# OZ440-SE100-CAR003_sheet14.net
KiCad netlist of a schematic drawn in Altium Designer
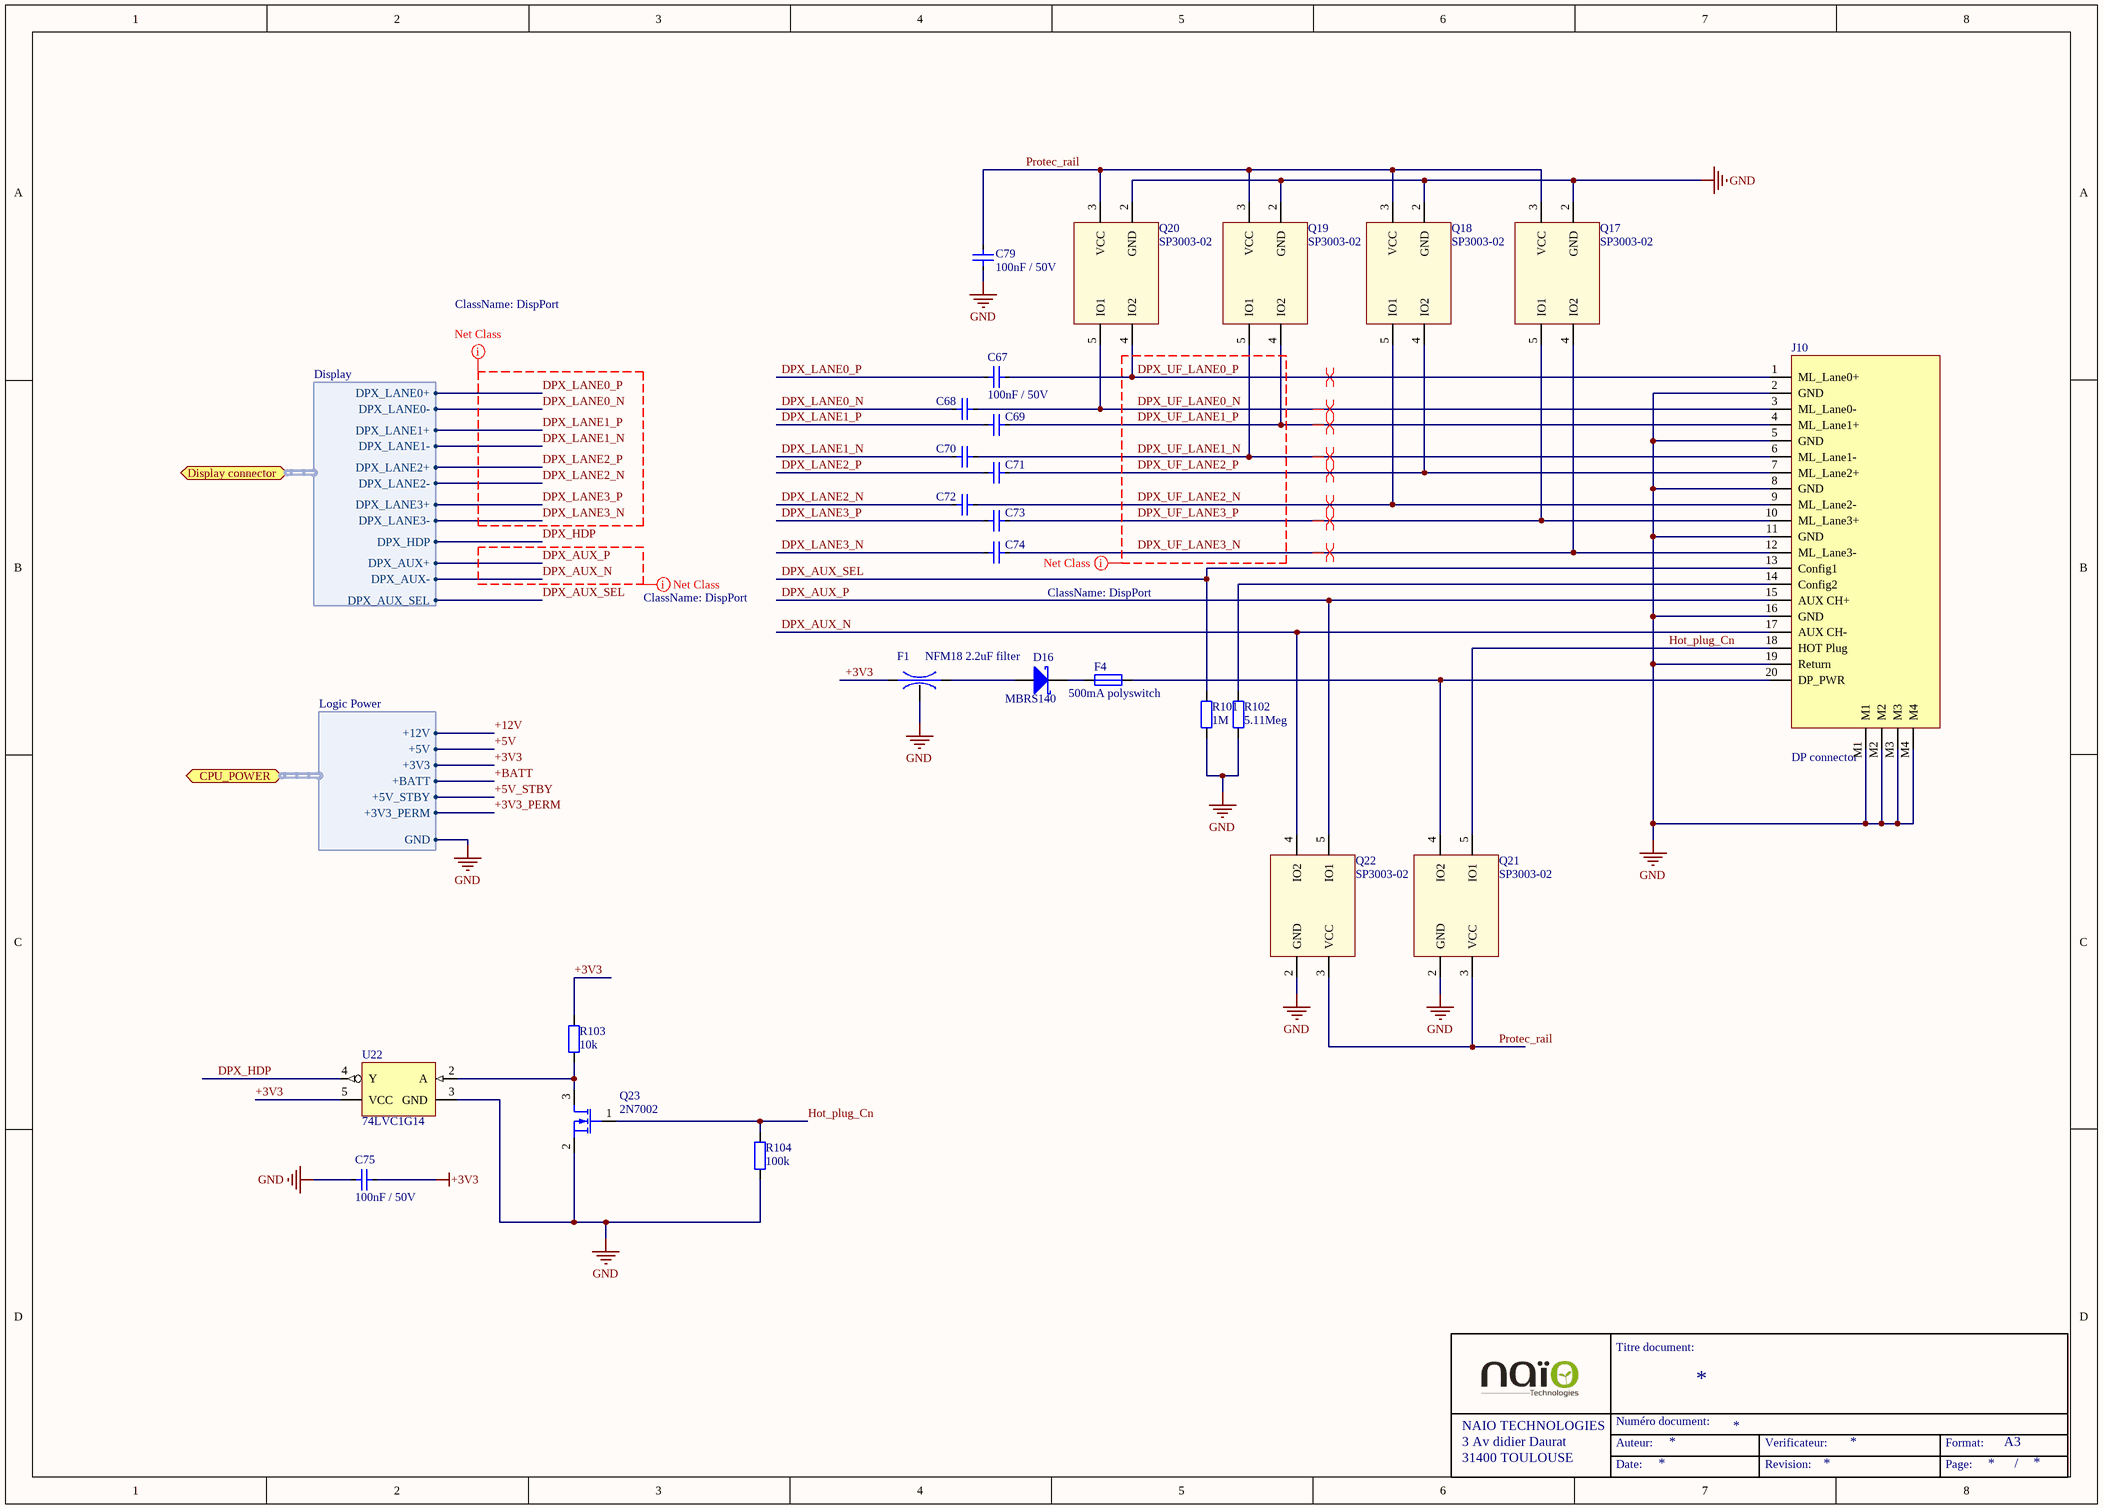
[diagram p0: OZ440-SE100-CAR003_sheet14.SchDoc]

(export (version "E")
  (design (tool "Eeschema 10.0.6"))
  (components
    (comp (ref "C67")
      (value "CAP-SMD")
      (footprint "C0805-STD")
      (description "0805 100nF / 50V  X7R ceramic capacitor")
      (fields
        (field (name "DISPLAYED REFERENCE") "100nF / 50V")
        (field (name "TOLERANCE") "+/- 10%")
        (field (name "MANUFACTURER") "vishay")
      )
      (libsource (lib "lib_NAIO") (part "CAP-SMD"))
    )
    (comp (ref "C68")
      (value "CAP-SMD")
      (footprint "C0805-STD")
      (description "0805 100nF / 50V  X7R ceramic capacitor")
      (fields (field (name "TOLERANCE") "+/- 10%") (field (name "MANUFACTURER") "vishay"))
      (libsource (lib "lib_NAIO") (part "CAP-SMD"))
    )
    (comp (ref "C69")
      (value "CAP-SMD")
      (footprint "C0805-STD")
      (description "0805 100nF / 50V  X7R ceramic capacitor")
      (fields (field (name "TOLERANCE") "+/- 10%") (field (name "MANUFACTURER") "vishay"))
      (libsource (lib "lib_NAIO") (part "CAP-SMD"))
    )
    (comp (ref "C70")
      (value "CAP-SMD")
      (footprint "C0805-STD")
      (description "0805 100nF / 50V  X7R ceramic capacitor")
      (fields (field (name "TOLERANCE") "+/- 10%") (field (name "MANUFACTURER") "vishay"))
      (libsource (lib "lib_NAIO") (part "CAP-SMD"))
    )
    (comp (ref "C71")
      (value "CAP-SMD")
      (footprint "C0805-STD")
      (description "0805 100nF / 50V  X7R ceramic capacitor")
      (fields (field (name "TOLERANCE") "+/- 10%") (field (name "MANUFACTURER") "vishay"))
      (libsource (lib "lib_NAIO") (part "CAP-SMD"))
    )
    (comp (ref "C72")
      (value "CAP-SMD")
      (footprint "C0805-STD")
      (description "0805 100nF / 50V  X7R ceramic capacitor")
      (fields (field (name "TOLERANCE") "+/- 10%") (field (name "MANUFACTURER") "vishay"))
      (libsource (lib "lib_NAIO") (part "CAP-SMD"))
    )
    (comp (ref "C73")
      (value "CAP-SMD")
      (footprint "C0805-STD")
      (description "0805 100nF / 50V  X7R ceramic capacitor")
      (fields (field (name "TOLERANCE") "+/- 10%") (field (name "MANUFACTURER") "vishay"))
      (libsource (lib "lib_NAIO") (part "CAP-SMD"))
    )
    (comp (ref "C74")
      (value "CAP-SMD")
      (footprint "C0805-STD")
      (description "0805 100nF / 50V  X7R ceramic capacitor")
      (fields (field (name "TOLERANCE") "+/- 10%") (field (name "MANUFACTURER") "vishay"))
      (libsource (lib "lib_NAIO") (part "CAP-SMD"))
    )
    (comp (ref "C75")
      (value "CAP-SMD")
      (footprint "C0805-STD")
      (description "0805 100nF / 50V  X7R ceramic capacitor")
      (fields
        (field (name "DISPLAYED REFERENCE") "100nF / 50V")
        (field (name "TOLERANCE") "+/- 10%")
        (field (name "MANUFACTURER") "vishay")
      )
      (libsource (lib "lib_NAIO") (part "CAP-SMD"))
    )
    (comp (ref "C79")
      (value "CAP-SMD")
      (footprint "C0805-STD")
      (description "0805 100nF / 50V  X7R ceramic capacitor")
      (fields
        (field (name "DISPLAYED REFERENCE") "100nF / 50V")
        (field (name "TOLERANCE") "+/- 10%")
        (field (name "MANUFACTURER") "vishay")
      )
      (libsource (lib "lib_NAIO") (part "CAP-SMD"))
    )
    (comp (ref "D16")
      (value "DIODE_SCHOTKY-DO214AA")
      (footprint "DO214AA-STD")
      (description "1A/40V shottky diode in SMB package")
      (fields (field (name "DISPLAYED REFERENCE") "MBRS140") (field (name "MANUFACTURER") "FAIRCHILD"))
      (libsource (lib "lib_NAIO") (part "DIODE_SCHOTKY-DO214AA"))
    )
    (comp (ref "F1")
      (value "LC_FILTER-STD")
      (footprint "LC_0603-STD")
      (description "2A LC filter")
      (fields
        (field (name "DISPLAYED REFERENCE") "NFM18 2.2uF filter")
        (field (name "MANUFACTURER") "MURATA")
      )
      (libsource (lib "lib_NAIO") (part "LC_FILTER-STD"))
    )
    (comp (ref "F4")
      (value "FUSE-SMD")
      (footprint "R0805-STD")
      (description "0805 500mA resettable fuse")
      (fields (field (name "DISPLAYED REFERENCE") "500mA polyswitch") (field (name "MANUFACTURER") "BOURNS"))
      (libsource (lib "lib_NAIO") (part "FUSE-SMD"))
    )
    (comp (ref "J10")
      (value "CONN-STD-DISPLAY_PORT_B")
      (footprint "CONN-SPE-DISPLAY_PORT_DP1RD20JQ1R400_JAE")
      (description "Display port PCB connector")
      (fields (field (name "DISPLAYED REFERENCE") "DP connector") (field (name "MANUFACTURER") "JAE"))
      (libsource (lib "lib_NAIO") (part "CONN-STD-DISPLAY_PORT_B"))
    )
    (comp (ref "Q17")
      (value "SP03003_02-SC70")
      (footprint "SC70-SPE-SP3003")
      (description "Low capacitance ESD TVS")
      (fields (field (name "DISPLAYED REFERENCE") "SP3003-02") (field (name "MANUFACTURER") "LITTLEFUSE"))
      (libsource (lib "lib_NAIO") (part "SP03003_02-SC70"))
    )
    (comp (ref "Q18")
      (value "SP03003_02-SC70")
      (footprint "SC70-SPE-SP3003")
      (description "Low capacitance ESD TVS")
      (fields (field (name "DISPLAYED REFERENCE") "SP3003-02") (field (name "MANUFACTURER") "LITTLEFUSE"))
      (libsource (lib "lib_NAIO") (part "SP03003_02-SC70"))
    )
    (comp (ref "Q19")
      (value "SP03003_02-SC70")
      (footprint "SC70-SPE-SP3003")
      (description "Low capacitance ESD TVS")
      (fields (field (name "DISPLAYED REFERENCE") "SP3003-02") (field (name "MANUFACTURER") "LITTLEFUSE"))
      (libsource (lib "lib_NAIO") (part "SP03003_02-SC70"))
    )
    (comp (ref "Q20")
      (value "SP03003_02-SC70")
      (footprint "SC70-SPE-SP3003")
      (description "Low capacitance ESD TVS")
      (fields (field (name "DISPLAYED REFERENCE") "SP3003-02") (field (name "MANUFACTURER") "LITTLEFUSE"))
      (libsource (lib "lib_NAIO") (part "SP03003_02-SC70"))
    )
    (comp (ref "Q21")
      (value "SP03003_02-SC70")
      (footprint "SC70-SPE-SP3003")
      (description "Low capacitance ESD TVS")
      (fields (field (name "DISPLAYED REFERENCE") "SP3003-02") (field (name "MANUFACTURER") "LITTLEFUSE"))
      (libsource (lib "") (part "SP03003_02-SC70_1"))
    )
    (comp (ref "Q22")
      (value "SP03003_02-SC70")
      (footprint "SC70-SPE-SP3003")
      (description "Low capacitance ESD TVS")
      (fields (field (name "DISPLAYED REFERENCE") "SP3003-02") (field (name "MANUFACTURER") "LITTLEFUSE"))
      (libsource (lib "") (part "SP03003_02-SC70_1"))
    )
    (comp (ref "Q23")
      (value "2N7002-SMD3P")
      (footprint "SOT23-SPE-2N7002")
      (description "N-Channel Enhancement Mode Field Effect Transistor")
      (fields (field (name "DISPLAYED REFERENCE") "2N7002") (field (name "MANUFACTURER") "FAIRCHILD"))
      (libsource (lib "lib_NAIO") (part "2N7002-SMD3P"))
    )
    (comp (ref "R101")
      (value "RES-SMD")
      (footprint "R0805-STD")
      (description "1Mohm 1% 0805 SMD resistor")
      (fields
        (field (name "DISPLAYED REFERENCE") "1M")
        (field (name "TOLERANCE") "1%")
        (field (name "MANUFACTURER") "Vishay")
      )
      (libsource (lib "lib_NAIO") (part "RES-SMD"))
    )
    (comp (ref "R102")
      (value "RES-SMD")
      (footprint "R0805-STD")
      (description "5.11Meg Ohm 0805 SMD resistor")
      (fields
        (field (name "DISPLAYED REFERENCE") "5.11Meg")
        (field (name "TOLERANCE") "1%")
        (field (name "MANUFACTURER") "Vishay")
      )
      (libsource (lib "lib_NAIO") (part "RES-SMD"))
    )
    (comp (ref "R103")
      (value "RES-SMD")
      (footprint "R0805-STD")
      (description "10k Ohm 0805 SMD resistor")
      (fields
        (field (name "DISPLAYED REFERENCE") "10k")
        (field (name "TOLERANCE") "1 %")
        (field (name "MANUFACTURER") "Vishay")
      )
      (libsource (lib "lib_NAIO") (part "RES-SMD"))
    )
    (comp (ref "R104")
      (value "RES-SMD")
      (footprint "R0805-STD")
      (description "100k Ohm 0805 SMD resistor")
      (fields
        (field (name "DISPLAYED REFERENCE") "100k")
        (field (name "TOLERANCE") "1 %")
        (field (name "MANUFACTURER") "Vishay")
      )
      (libsource (lib "lib_NAIO") (part "RES-SMD"))
    )
    (comp (ref "U22")
      (value "74xxx1G14GW-SOT353-1")
      (footprint "SOT353-1_5pin-STD")
      (description "smith trigger inverter")
      (fields (field (name "DISPLAYED REFERENCE") "74LVC1G14") (field (name "MANUFACTURER") "NXP"))
      (libsource (lib "lib_NAIO") (part "74xxx1G14GW-SOT353-1"))
    )
  )
  (nets
    (net (code "4") (name "+3V3") (class "Default")
      (node (ref "C75") (pin "2") (pinfunction "2_2") (pintype "passive"))
      (node (ref "F1") (pin "1") (pinfunction "A_1") (pintype "passive"))
      (node (ref "R103") (pin "2") (pinfunction "2_2") (pintype "passive"))
      (node (ref "U22") (pin "5") (pinfunction "VCC_5") (pintype "power_in"))
    )
    (net (code "10") (name "/DPX_AUX_N") (class "Default")
      (node (ref "J10") (pin "17") (pinfunction "AUX_CH-_17") (pintype "passive"))
      (node (ref "Q22") (pin "4") (pinfunction "IO2_4") (pintype "passive"))
    )
    (net (code "11") (name "/DPX_AUX_P") (class "Default")
      (node (ref "J10") (pin "15") (pinfunction "AUX_CH+_15") (pintype "passive"))
      (node (ref "Q22") (pin "5") (pinfunction "IO1_5") (pintype "passive"))
    )
    (net (code "12") (name "/DPX_AUX_SEL") (class "Default")
      (node (ref "J10") (pin "13") (pinfunction "Config1_13") (pintype "passive"))
      (node (ref "R101") (pin "2") (pinfunction "2_2") (pintype "passive"))
    )
    (net (code "13") (name "/DPX_HDP") (class "Default")
      (node (ref "U22") (pin "4") (pinfunction "Y_4") (pintype "output"))
    )
    (net (code "14") (name "/DPX_LANE0_N") (class "Default")
      (node (ref "C68") (pin "2") (pinfunction "2_2") (pintype "passive"))
    )
    (net (code "15") (name "/DPX_LANE0_P") (class "Default")
      (node (ref "C67") (pin "2") (pinfunction "2_2") (pintype "passive"))
    )
    (net (code "16") (name "/DPX_LANE1_N") (class "Default")
      (node (ref "C70") (pin "2") (pinfunction "2_2") (pintype "passive"))
    )
    (net (code "17") (name "/DPX_LANE1_P") (class "Default")
      (node (ref "C69") (pin "2") (pinfunction "2_2") (pintype "passive"))
    )
    (net (code "18") (name "/DPX_LANE2_N") (class "Default")
      (node (ref "C72") (pin "2") (pinfunction "2_2") (pintype "passive"))
    )
    (net (code "19") (name "/DPX_LANE2_P") (class "Default")
      (node (ref "C71") (pin "2") (pinfunction "2_2") (pintype "passive"))
    )
    (net (code "20") (name "/DPX_LANE3_N") (class "Default")
      (node (ref "C74") (pin "2") (pinfunction "2_2") (pintype "passive"))
    )
    (net (code "21") (name "/DPX_LANE3_P") (class "Default")
      (node (ref "C73") (pin "2") (pinfunction "2_2") (pintype "passive"))
    )
    (net (code "22") (name "/DPX_UF_LANE0_N") (class "Default")
      (node (ref "C68") (pin "1") (pinfunction "1_1") (pintype "passive"))
      (node (ref "J10") (pin "3") (pinfunction "ML_Lane0-_3") (pintype "passive"))
      (node (ref "Q20") (pin "5") (pinfunction "IO1_5") (pintype "passive"))
    )
    (net (code "23") (name "/DPX_UF_LANE0_P") (class "Default")
      (node (ref "C67") (pin "1") (pinfunction "1_1") (pintype "passive"))
      (node (ref "J10") (pin "1") (pinfunction "ML_Lane0+_1") (pintype "passive"))
      (node (ref "Q20") (pin "4") (pinfunction "IO2_4") (pintype "passive"))
    )
    (net (code "24") (name "/DPX_UF_LANE1_N") (class "Default")
      (node (ref "C70") (pin "1") (pinfunction "1_1") (pintype "passive"))
      (node (ref "J10") (pin "6") (pinfunction "ML_Lane1-_6") (pintype "passive"))
      (node (ref "Q19") (pin "5") (pinfunction "IO1_5") (pintype "passive"))
    )
    (net (code "25") (name "/DPX_UF_LANE1_P") (class "Default")
      (node (ref "C69") (pin "1") (pinfunction "1_1") (pintype "passive"))
      (node (ref "J10") (pin "4") (pinfunction "ML_Lane1+_4") (pintype "passive"))
      (node (ref "Q19") (pin "4") (pinfunction "IO2_4") (pintype "passive"))
    )
    (net (code "26") (name "/DPX_UF_LANE2_N") (class "Default")
      (node (ref "C72") (pin "1") (pinfunction "1_1") (pintype "passive"))
      (node (ref "J10") (pin "9") (pinfunction "ML_Lane2-_9") (pintype "passive"))
      (node (ref "Q18") (pin "5") (pinfunction "IO1_5") (pintype "passive"))
    )
    (net (code "27") (name "/DPX_UF_LANE2_P") (class "Default")
      (node (ref "C71") (pin "1") (pinfunction "1_1") (pintype "passive"))
      (node (ref "J10") (pin "7") (pinfunction "ML_Lane2+_7") (pintype "passive"))
      (node (ref "Q18") (pin "4") (pinfunction "IO2_4") (pintype "passive"))
    )
    (net (code "28") (name "/DPX_UF_LANE3_N") (class "Default")
      (node (ref "C74") (pin "1") (pinfunction "1_1") (pintype "passive"))
      (node (ref "J10") (pin "12") (pinfunction "ML_Lane3-_12") (pintype "passive"))
      (node (ref "Q17") (pin "4") (pinfunction "IO2_4") (pintype "passive"))
    )
    (net (code "29") (name "/DPX_UF_LANE3_P") (class "Default")
      (node (ref "C73") (pin "1") (pinfunction "1_1") (pintype "passive"))
      (node (ref "J10") (pin "10") (pinfunction "ML_Lane3+_10") (pintype "passive"))
      (node (ref "Q17") (pin "5") (pinfunction "IO1_5") (pintype "passive"))
    )
    (net (code "30") (name "/Hot_plug_Cn") (class "Default")
      (node (ref "J10") (pin "18") (pinfunction "HOT_Plug_18") (pintype "passive"))
      (node (ref "Q21") (pin "5") (pinfunction "IO1_5") (pintype "passive"))
      (node (ref "Q23") (pin "1") (pinfunction "G_1") (pintype "passive"))
      (node (ref "R104") (pin "2") (pinfunction "2_2") (pintype "passive"))
    )
    (net (code "31") (name "/Protec_rail") (class "Default")
      (node (ref "C79") (pin "2") (pinfunction "2_2") (pintype "passive"))
      (node (ref "Q17") (pin "3") (pinfunction "VCC_3") (pintype "passive"))
      (node (ref "Q18") (pin "3") (pinfunction "VCC_3") (pintype "passive"))
      (node (ref "Q19") (pin "3") (pinfunction "VCC_3") (pintype "passive"))
      (node (ref "Q20") (pin "3") (pinfunction "VCC_3") (pintype "passive"))
      (node (ref "Q21") (pin "3") (pinfunction "VCC_3") (pintype "passive"))
      (node (ref "Q22") (pin "3") (pinfunction "VCC_3") (pintype "passive"))
    )
    (net (code "34") (name "GND") (class "Default")
      (node (ref "C75") (pin "1") (pinfunction "1_1") (pintype "passive"))
      (node (ref "C79") (pin "1") (pinfunction "1_1") (pintype "passive"))
      (node (ref "F1") (pin "3") (pinfunction "G_3") (pintype "passive"))
      (node (ref "J10") (pin "11") (pinfunction "GND_11") (pintype "passive"))
      (node (ref "J10") (pin "16") (pinfunction "GND_16") (pintype "passive"))
      (node (ref "J10") (pin "19") (pinfunction "Return_19") (pintype "passive"))
      (node (ref "J10") (pin "2") (pinfunction "GND_2") (pintype "passive"))
      (node (ref "J10") (pin "5") (pinfunction "GND_5") (pintype "passive"))
      (node (ref "J10") (pin "8") (pinfunction "GND_8") (pintype "passive"))
      (node (ref "J10") (pin "M1") (pinfunction "M1_M1") (pintype "passive"))
      (node (ref "J10") (pin "M2") (pinfunction "M2_M2") (pintype "passive"))
      (node (ref "J10") (pin "M3") (pinfunction "M3_M3") (pintype "passive"))
      (node (ref "J10") (pin "M4") (pinfunction "M4_M4") (pintype "passive"))
      (node (ref "Q17") (pin "2") (pinfunction "GND_2") (pintype "passive"))
      (node (ref "Q18") (pin "2") (pinfunction "GND_2") (pintype "passive"))
      (node (ref "Q19") (pin "2") (pinfunction "GND_2") (pintype "passive"))
      (node (ref "Q20") (pin "2") (pinfunction "GND_2") (pintype "passive"))
      (node (ref "Q21") (pin "2") (pinfunction "GND_2") (pintype "passive"))
      (node (ref "Q22") (pin "2") (pinfunction "GND_2") (pintype "passive"))
      (node (ref "Q23") (pin "2") (pinfunction "S_2") (pintype "passive"))
      (node (ref "R101") (pin "1") (pinfunction "1_1") (pintype "passive"))
      (node (ref "R102") (pin "1") (pinfunction "1_1") (pintype "passive"))
      (node (ref "R104") (pin "1") (pinfunction "1_1") (pintype "passive"))
      (node (ref "U22") (pin "3") (pinfunction "GND_3") (pintype "power_in"))
    )
    (net (code "35") (name "Net-(D16-PadK)") (class "Default")
      (node (ref "D16") (pin "K") (pinfunction "K_K") (pintype "passive"))
      (node (ref "F4") (pin "1") (pinfunction "1_1") (pintype "passive"))
    )
    (net (code "36") (name "Net-(F1-B)") (class "Default")
      (node (ref "D16") (pin "A") (pinfunction "A_A") (pintype "passive"))
      (node (ref "F1") (pin "2") (pinfunction "B_2") (pintype "passive"))
    )
    (net (code "37") (name "Net-(J10-Config2)") (class "Default")
      (node (ref "J10") (pin "14") (pinfunction "Config2_14") (pintype "passive"))
      (node (ref "R102") (pin "2") (pinfunction "2_2") (pintype "passive"))
    )
    (net (code "38") (name "Net-(J10-DP_PWR)") (class "Default")
      (node (ref "F4") (pin "2") (pinfunction "2_2") (pintype "passive"))
      (node (ref "J10") (pin "20") (pinfunction "DP_PWR_20") (pintype "passive"))
      (node (ref "Q21") (pin "4") (pinfunction "IO2_4") (pintype "passive"))
    )
    (net (code "39") (name "Net-(Q23-D)") (class "Default")
      (node (ref "Q23") (pin "3") (pinfunction "D_3") (pintype "passive"))
      (node (ref "R103") (pin "1") (pinfunction "1_1") (pintype "passive"))
      (node (ref "U22") (pin "2") (pinfunction "A_2") (pintype "input"))
    )
  )
)
